# Power_Supplies.net
KiCad netlist of a schematic drawn in Altium Designer
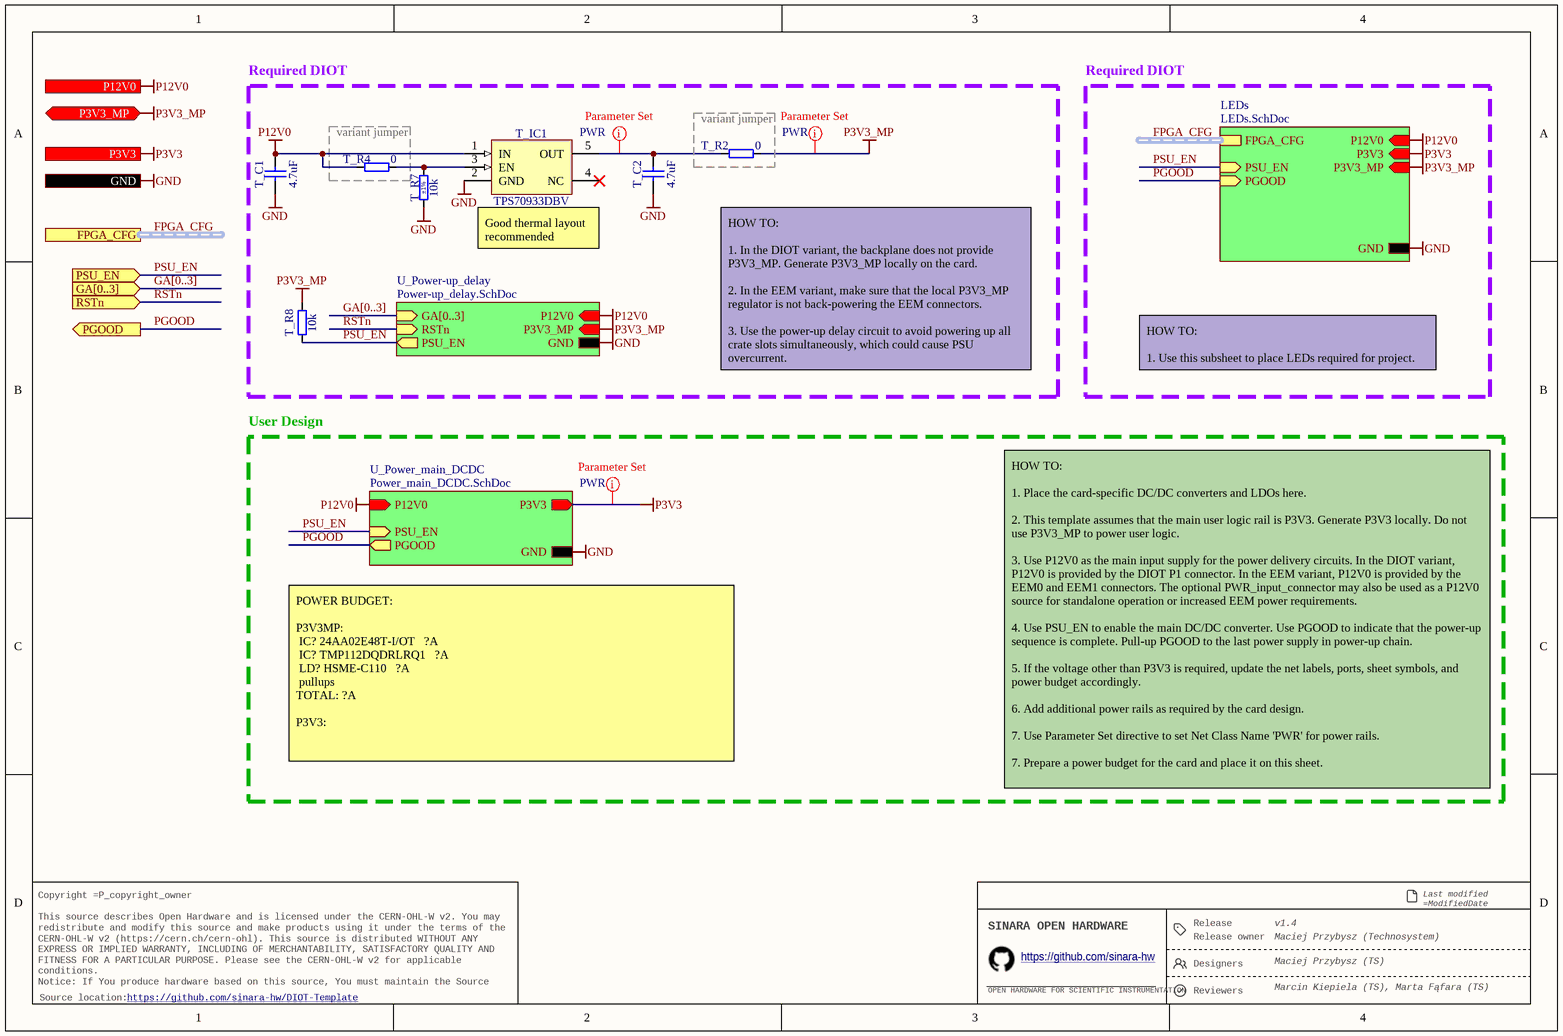
[diagram p0: Power_Supplies.SchDoc]

(export (version "E")
  (design (tool "Eeschema 10.0.6"))
  (components
    (comp (ref "T_C1")
      (value "4.7uF")
      (footprint "CAPC2012X135N")
      (description "Non-polarised capacitor")
      (fields
        (field (name "PART NUMBER") "CC0805_4.7UF_16V_10%_X7R")
        (field (name "VOLTAGE") "16V")
        (field (name "AUTHOR") "CERN DEM JLC")
      )
      (libsource (lib "Capacitors") (part "Capacitor - non polarized"))
    )
    (comp (ref "T_C2")
      (value "4.7uF")
      (footprint "CAPC2012X135N")
      (description "Non-polarised capacitor")
      (fields
        (field (name "PART NUMBER") "CC0805_4.7UF_16V_10%_X7R")
        (field (name "VOLTAGE") "16V")
        (field (name "AUTHOR") "CERN DEM JLC")
      )
      (libsource (lib "Capacitors") (part "Capacitor - non polarized"))
    )
    (comp (ref "T_IC1")
      (value "TPS70933DBV")
      (footprint "SOT95P280X145-5N")
      (description "150-mA, 30-V, 1-µA IQ Voltage Regulators with Enable")
      (fields (field (name "MANUFACTURER") "TEXAS INSTRUMENTS") (field (name "AUTHOR") "CERN DEM JLC"))
      (libsource (lib "ICs And Semiconductors") (part "TPS709"))
    )
    (comp (ref "T_R2")
      (value "0")
      (footprint "RESC1005X40N")
      (description "Resistor")
      (fields
        (field (name "PART NUMBER") "R0402_0R_JUMPER")
        (field (name "MANUFACTURER") "GENERIC")
        (field (name "AUTHOR") "CERN DEM JLC")
      )
      (libsource (lib "Resistors") (part "Resistor"))
    )
    (comp (ref "T_R4")
      (value "0")
      (footprint "RESC1005X40N")
      (description "Resistor")
      (fields
        (field (name "PART NUMBER") "R0402_0R_JUMPER")
        (field (name "MANUFACTURER") "GENERIC")
        (field (name "AUTHOR") "CERN DEM JLC")
      )
      (libsource (lib "Resistors") (part "Resistor"))
    )
    (comp (ref "T_R7")
      (value "10k")
      (footprint "RESC1005X40N")
      (description "Resistor - 1%")
      (fields
        (field (name "TOLERANCE") "±1%")
        (field (name "PART NUMBER") "R0402_10K_1%_0.0625W_100PPM")
        (field (name "POWER") "0.0625W")
        (field (name "AUTHOR") "CERN DEM JLC")
      )
      (libsource (lib "Resistors") (part "Resistor - 1%"))
    )
    (comp (ref "T_R8")
      (value "10k")
      (footprint "RESC1005X40N")
      (description "Resistor - 1%")
      (fields
        (field (name "PART NUMBER") "R0402_10K_1%_0.0625W_100PPM")
        (field (name "POWER") "0.0625W")
        (field (name "AUTHOR") "CERN DEM JLC")
      )
      (libsource (lib "Resistors") (part "Resistor - 1%"))
    )
  )
  (nets
    (net (code "8") (name "/PSU_EN") (class "Default")
      (node (ref "T_R8") (pin "1") (pinfunction "1_1") (pintype "passive"))
    )
    (net (code "11") (name "GND") (class "Default")
      (node (ref "T_C1") (pin "1") (pinfunction "1_1") (pintype "passive"))
      (node (ref "T_C2") (pin "1") (pinfunction "1_1") (pintype "passive"))
      (node (ref "T_IC1") (pin "2") (pinfunction "GND_2") (pintype "power_in"))
      (node (ref "T_R7") (pin "1") (pinfunction "1_1") (pintype "passive"))
    )
    (net (code "12") (name "Net-(T_IC1-EN)") (class "Default")
      (node (ref "T_IC1") (pin "3") (pinfunction "EN_3") (pintype "input"))
      (node (ref "T_R4") (pin "2") (pinfunction "2_2") (pintype "passive"))
      (node (ref "T_R7") (pin "2") (pinfunction "2_2") (pintype "passive"))
    )
    (net (code "13") (name "Net-(T_IC1-OUT)") (class "Default")
      (node (ref "T_C2") (pin "2") (pinfunction "2_2") (pintype "passive"))
      (node (ref "T_IC1") (pin "5") (pinfunction "OUT_5") (pintype "power_in"))
      (node (ref "T_R2") (pin "1") (pinfunction "1_1") (pintype "passive"))
    )
    (net (code "15") (name "P3V3_MP") (class "Default")
      (node (ref "T_R2") (pin "2") (pinfunction "2_2") (pintype "passive"))
      (node (ref "T_R8") (pin "2") (pinfunction "2_2") (pintype "passive"))
    )
    (net (code "16") (name "P12V0") (class "Default")
      (node (ref "T_C1") (pin "2") (pinfunction "2_2") (pintype "passive"))
      (node (ref "T_IC1") (pin "1") (pinfunction "IN_1") (pintype "input"))
      (node (ref "T_R4") (pin "1") (pinfunction "1_1") (pintype "passive"))
    )
    (net (code "17") (name "unconnected-(T_IC1-NC-Pad4)") (class "Default")
      (node (ref "T_IC1") (pin "4") (pinfunction "NC_4") (pintype "passive+no_connect"))
    )
  )
)
